# 17_-_PLUGS.net
KiCad netlist of a schematic drawn in Altium Designer
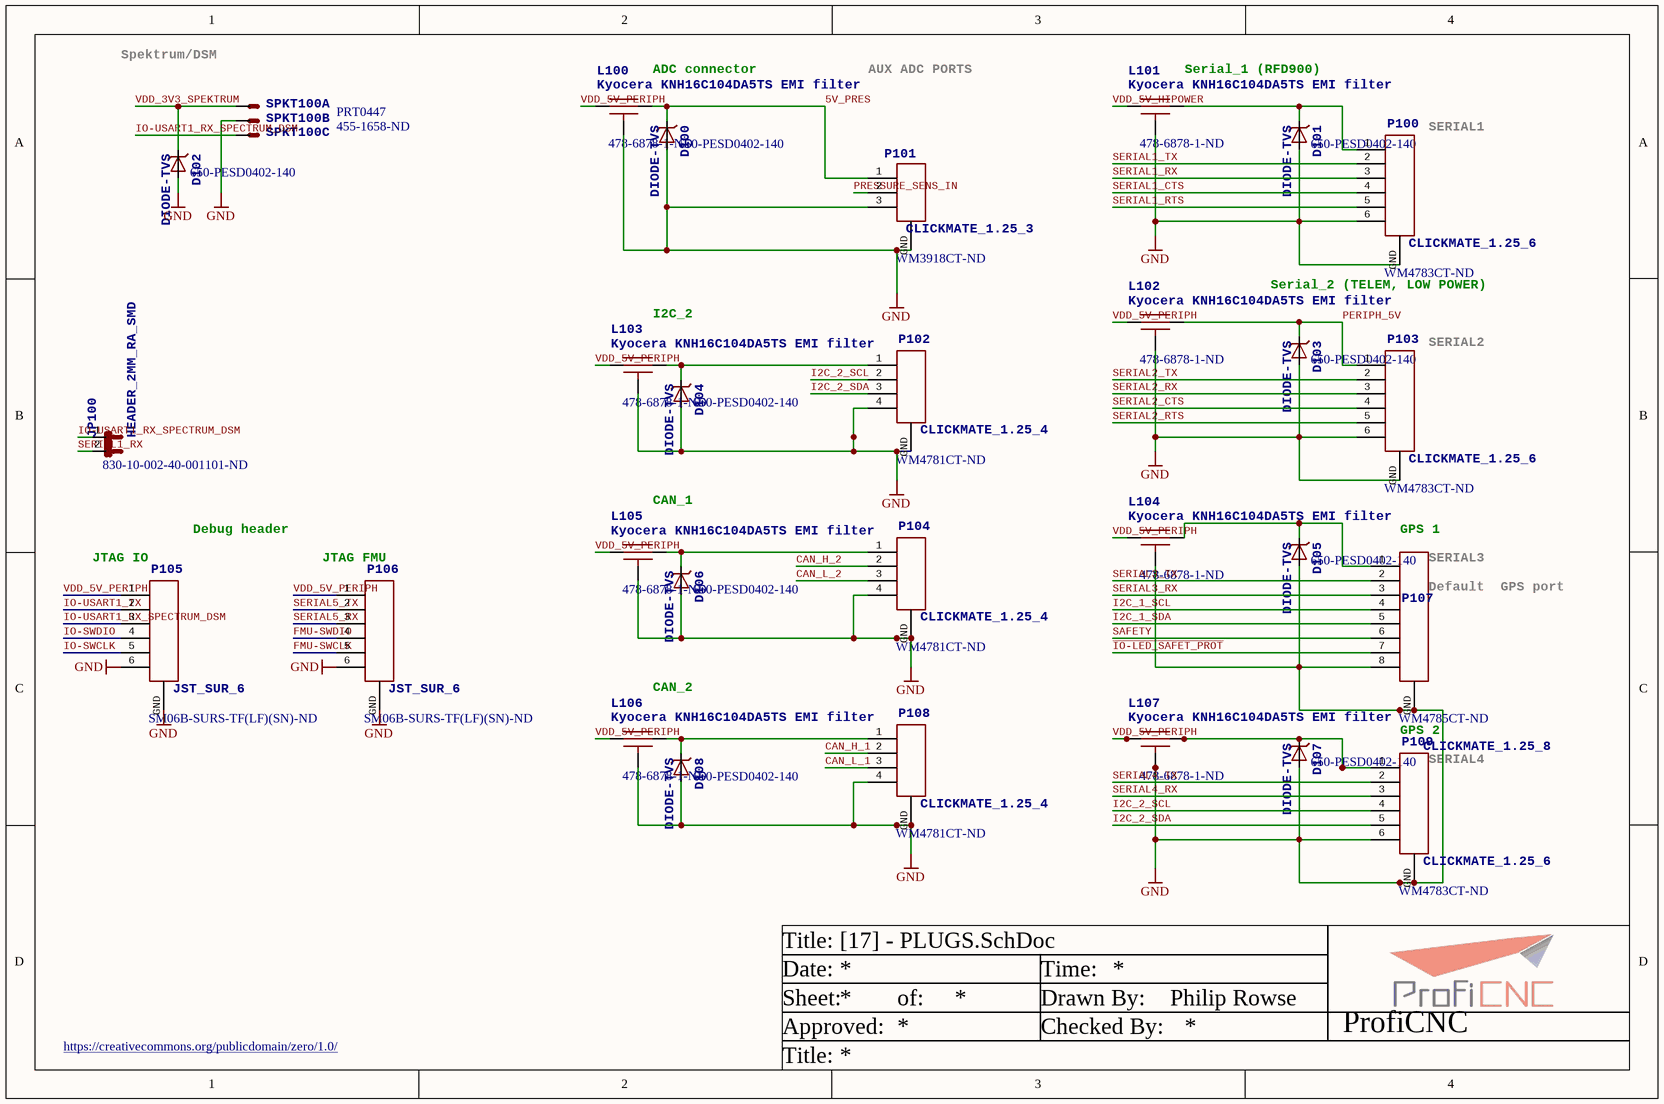
[diagram p0: [17] - PLUGS.SchDoc]

(export (version "E")
  (design (tool "Eeschema 10.0.6"))
  (components
    (comp (ref "D100")
      (value "DIODE-TVS")
      (footprint "0402-TVS")
      (description "Diode, TVS, 14VWM, 40VC, 0402, SMD")
      (fields
        (field (name "SUPPLIER PART NUMBER 1") "650-PESD0402-140")
        (field (name "3DR_PARTNO") "ECM0837")
      )
      (libsource (lib "PCA_0005_FULL_CB_REV_A") (part "DIODE-TVS"))
    )
    (comp (ref "D101")
      (value "DIODE-TVS")
      (footprint "0402-TVS")
      (description "Diode, TVS, 14VWM, 40VC, 0402, SMD")
      (fields
        (field (name "SUPPLIER PART NUMBER 1") "650-PESD0402-140")
        (field (name "3DR_PARTNO") "ECM0837")
      )
      (libsource (lib "PCA_0005_FULL_CB_REV_A") (part "DIODE-TVS"))
    )
    (comp (ref "D102")
      (value "DIODE-TVS")
      (footprint "0402-TVS")
      (description "Diode, TVS, 14VWM, 40VC, 0402, SMD")
      (fields
        (field (name "SUPPLIER PART NUMBER 1") "650-PESD0402-140")
        (field (name "3DR_PARTNO") "ECM0837")
      )
      (libsource (lib "PCA_0005_FULL_CB_REV_A") (part "DIODE-TVS"))
    )
    (comp (ref "D103")
      (value "DIODE-TVS")
      (footprint "0402-TVS")
      (description "Diode, TVS, 14VWM, 40VC, 0402, SMD")
      (fields
        (field (name "SUPPLIER PART NUMBER 1") "650-PESD0402-140")
        (field (name "3DR_PARTNO") "ECM0837")
      )
      (libsource (lib "PCA_0005_FULL_CB_REV_A") (part "DIODE-TVS"))
    )
    (comp (ref "D104")
      (value "DIODE-TVS")
      (footprint "0402-TVS")
      (description "Diode, TVS, 14VWM, 40VC, 0402, SMD")
      (fields
        (field (name "SUPPLIER PART NUMBER 1") "650-PESD0402-140")
        (field (name "3DR_PARTNO") "ECM0837")
      )
      (libsource (lib "PCA_0005_FULL_CB_REV_A") (part "DIODE-TVS"))
    )
    (comp (ref "D105")
      (value "DIODE-TVS")
      (footprint "0402-TVS")
      (description "Diode, TVS, 14VWM, 40VC, 0402, SMD")
      (fields
        (field (name "SUPPLIER PART NUMBER 1") "650-PESD0402-140")
        (field (name "3DR_PARTNO") "ECM0837")
      )
      (libsource (lib "PCA_0005_FULL_CB_REV_A") (part "DIODE-TVS"))
    )
    (comp (ref "D106")
      (value "DIODE-TVS")
      (footprint "0402-TVS")
      (description "Diode, TVS, 14VWM, 40VC, 0402, SMD")
      (fields
        (field (name "SUPPLIER PART NUMBER 1") "650-PESD0402-140")
        (field (name "3DR_PARTNO") "ECM0837")
      )
      (libsource (lib "PCA_0005_FULL_CB_REV_A") (part "DIODE-TVS"))
    )
    (comp (ref "D107")
      (value "DIODE-TVS")
      (footprint "0402-TVS")
      (description "Diode, TVS, 14VWM, 40VC, 0402, SMD")
      (fields
        (field (name "SUPPLIER PART NUMBER 1") "650-PESD0402-140")
        (field (name "3DR_PARTNO") "ECM0837")
      )
      (libsource (lib "PCA_0005_FULL_CB_REV_A") (part "DIODE-TVS"))
    )
    (comp (ref "D108")
      (value "DIODE-TVS")
      (footprint "0402-TVS")
      (description "Diode, TVS, 14VWM, 40VC, 0402, SMD")
      (fields
        (field (name "SUPPLIER PART NUMBER 1") "650-PESD0402-140")
        (field (name "3DR_PARTNO") "ECM0837")
      )
      (libsource (lib "PCA_0005_FULL_CB_REV_A") (part "DIODE-TVS"))
    )
    (comp (ref "JP100")
      (value "HEADER_2MM_RA_SMD")
      (footprint "HEADER_2MM_RA_2")
      (description "Connector, PCB, 2MM, 2Pos, R/A, SMD, Au")
      (fields
        (field (name "PARTNO") "830-10-002-40-001101")
        (field (name "SUPPLIER PART NUMBER 1") "830-10-002-40-001101-ND")
        (field (name "3DR_PARTNO") "PRT0437")
      )
      (libsource (lib "PCA_0005_FULL_CB_REV_A") (part "HEADER_2MM_RA_SMD"))
    )
    (comp (ref "L100")
      (value "Kyocera KNH16C104DA5TS EMI filter")
      (footprint "KYOCERA-KNH16-DA")
      (description "Capacitor, Filter, 0.1uF, 25V, 2A, 0603, SMD")
      (fields (field (name "SUPPLIER PART NUMBER 1") "478-6878-1-ND") (field (name "3DR_PARTNO") "ECM0719"))
      (libsource (lib "PCA_0005_FULL_CB_REV_A") (part "KNH16C104DA5TS"))
    )
    (comp (ref "L101")
      (value "Kyocera KNH16C104DA5TS EMI filter")
      (footprint "KYOCERA-KNH16-DA")
      (description "Capacitor, Filter, 0.1uF, 25V, 2A, 0603, SMD")
      (fields (field (name "SUPPLIER PART NUMBER 1") "478-6878-1-ND") (field (name "3DR_PARTNO") "ECM0719"))
      (libsource (lib "PCA_0005_FULL_CB_REV_A") (part "KNH16C104DA5TS"))
    )
    (comp (ref "L102")
      (value "Kyocera KNH16C104DA5TS EMI filter")
      (footprint "KYOCERA-KNH16-DA")
      (description "Capacitor, Filter, 0.1uF, 25V, 2A, 0603, SMD")
      (fields (field (name "SUPPLIER PART NUMBER 1") "478-6878-1-ND") (field (name "3DR_PARTNO") "ECM0719"))
      (libsource (lib "PCA_0005_FULL_CB_REV_A") (part "KNH16C104DA5TS"))
    )
    (comp (ref "L103")
      (value "Kyocera KNH16C104DA5TS EMI filter")
      (footprint "KYOCERA-KNH16-DA")
      (description "Capacitor, Filter, 0.1uF, 25V, 2A, 0603, SMD")
      (fields (field (name "SUPPLIER PART NUMBER 1") "478-6878-1-ND") (field (name "3DR_PARTNO") "ECM0719"))
      (libsource (lib "PCA_0005_FULL_CB_REV_A") (part "KNH16C104DA5TS"))
    )
    (comp (ref "L104")
      (value "Kyocera KNH16C104DA5TS EMI filter")
      (footprint "KYOCERA-KNH16-DA")
      (description "Capacitor, Filter, 0.1uF, 25V, 2A, 0603, SMD")
      (fields (field (name "SUPPLIER PART NUMBER 1") "478-6878-1-ND") (field (name "3DR_PARTNO") "ECM0719"))
      (libsource (lib "PCA_0005_FULL_CB_REV_A") (part "KNH16C104DA5TS"))
    )
    (comp (ref "L105")
      (value "Kyocera KNH16C104DA5TS EMI filter")
      (footprint "KYOCERA-KNH16-DA")
      (description "Capacitor, Filter, 0.1uF, 25V, 2A, 0603, SMD")
      (fields (field (name "SUPPLIER PART NUMBER 1") "478-6878-1-ND") (field (name "3DR_PARTNO") "ECM0719"))
      (libsource (lib "PCA_0005_FULL_CB_REV_A") (part "KNH16C104DA5TS"))
    )
    (comp (ref "L106")
      (value "Kyocera KNH16C104DA5TS EMI filter")
      (footprint "KYOCERA-KNH16-DA")
      (description "Capacitor, Filter, 0.1uF, 25V, 2A, 0603, SMD")
      (fields (field (name "SUPPLIER PART NUMBER 1") "478-6878-1-ND") (field (name "3DR_PARTNO") "ECM0719"))
      (libsource (lib "PCA_0005_FULL_CB_REV_A") (part "KNH16C104DA5TS"))
    )
    (comp (ref "L107")
      (value "Kyocera KNH16C104DA5TS EMI filter")
      (footprint "KYOCERA-KNH16-DA")
      (description "Capacitor, Filter, 0.1uF, 25V, 2A, 0603, SMD")
      (fields (field (name "SUPPLIER PART NUMBER 1") "478-6878-1-ND") (field (name "3DR_PARTNO") "ECM0719"))
      (libsource (lib "PCA_0005_FULL_CB_REV_A") (part "KNH16C104DA5TS"))
    )
    (comp (ref "P100")
      (value "CLICKMATE_1.25_6")
      (footprint "CLICKMATE_V6")
      (description "Connector, Rcpt, 6Pos, 1.25MM, W/B, VERT, SMD, Tin")
      (fields (field (name "SUPPLIER PART NUMBER 1") "WM4783CT-ND") (field (name "3DR_PARTNO") "PRT0439"))
      (libsource (lib "PCA_0005_FULL_CB_REV_A") (part "CLICKMATE_1.25_6"))
    )
    (comp (ref "P101")
      (value "CLICKMATE_1.25_3")
      (footprint "CLICKMATE_V3")
      (description "Connector, Rcpt,1.25MM,W/B,SGL,S/T,3CKT,SMD,Tin")
      (fields (field (name "SUPPLIER PART NUMBER 1") "WM3918CT-ND") (field (name "3DR_PARTNO") "PRT0440"))
      (libsource (lib "PCA_0005_FULL_CB_REV_A") (part "CLICKMATE_1.25_3"))
    )
    (comp (ref "P102")
      (value "CLICKMATE_1.25_4")
      (footprint "CLICKMATE_V4")
      (description "Connector, Rcpt, 4Pos, 1.25MM, W/B, VERT, SMD, Tin")
      (fields (field (name "SUPPLIER PART NUMBER 1") "WM4781CT-ND") (field (name "3DR_PARTNO") "PRT0441"))
      (libsource (lib "PCA_0005_FULL_CB_REV_A") (part "CLICKMATE_1.25_4"))
    )
    (comp (ref "P103")
      (value "CLICKMATE_1.25_6")
      (footprint "CLICKMATE_V6")
      (description "Connector, Rcpt, 6Pos, 1.25MM, W/B, VERT, SMD, Tin")
      (fields (field (name "SUPPLIER PART NUMBER 1") "WM4783CT-ND") (field (name "3DR_PARTNO") "PRT0439"))
      (libsource (lib "PCA_0005_FULL_CB_REV_A") (part "CLICKMATE_1.25_6"))
    )
    (comp (ref "P104")
      (value "CLICKMATE_1.25_4")
      (footprint "CLICKMATE_V4")
      (description "Connector, Rcpt, 4Pos, 1.25MM, W/B, VERT, SMD, Tin")
      (fields (field (name "SUPPLIER PART NUMBER 1") "WM4781CT-ND") (field (name "3DR_PARTNO") "PRT0441"))
      (libsource (lib "PCA_0005_FULL_CB_REV_A") (part "CLICKMATE_1.25_4"))
    )
    (comp (ref "P105")
      (value "JST_SUR_6")
      (footprint "JST_SUR_H6")
      (description "Connector, Header, 6Pos, .8mm IDC, R/A, SMD, Tin")
      (fields
        (field (name "SUPPLIER PART NUMBER 1") "SM06B-SURS-TF(LF)(SN)-ND")
        (field (name "3DR_PARTNO") "PRT0442")
      )
      (libsource (lib "PCA_0005_FULL_CB_REV_A") (part "JST_SUR_6"))
    )
    (comp (ref "P106")
      (value "JST_SUR_6")
      (footprint "JST_SUR_H6")
      (description "Connector, Header, 6Pos, .8mm IDC, R/A, SMD, Tin")
      (fields
        (field (name "SUPPLIER PART NUMBER 1") "SM06B-SURS-TF(LF)(SN)-ND")
        (field (name "3DR_PARTNO") "PRT0442")
      )
      (libsource (lib "PCA_0005_FULL_CB_REV_A") (part "JST_SUR_6"))
    )
    (comp (ref "P107")
      (value "CLICKMATE_1.25_8")
      (footprint "CLICKMATE_V8")
      (description "Connector, Rcpt, 8Pos, 1.25MM, W/B, VERT, SMD, Tin")
      (fields (field (name "SUPPLIER PART NUMBER 1") "WM4785CT-ND") (field (name "3DR_PARTNO") "PRT0443"))
      (libsource (lib "PCA_0005_FULL_CB_REV_A") (part "CLICKMATE_1.25_8"))
    )
    (comp (ref "P108")
      (value "CLICKMATE_1.25_4")
      (footprint "CLICKMATE_V4")
      (description "Connector, Rcpt, 4Pos, 1.25MM, W/B, VERT, SMD, Tin")
      (fields (field (name "SUPPLIER PART NUMBER 1") "WM4781CT-ND") (field (name "3DR_PARTNO") "PRT0441"))
      (libsource (lib "PCA_0005_FULL_CB_REV_A") (part "CLICKMATE_1.25_4"))
    )
    (comp (ref "P109")
      (value "CLICKMATE_1.25_6")
      (footprint "CLICKMATE_V6")
      (description "Connector, Rcpt, 6Pos, 1.25MM, W/B, VERT, SMD, Tin")
      (fields (field (name "SUPPLIER PART NUMBER 1") "WM4783CT-ND") (field (name "3DR_PARTNO") "PRT0439"))
      (libsource (lib "PCA_0005_FULL_CB_REV_A") (part "CLICKMATE_1.25_6"))
    )
    (comp (ref "SPKT100")
      (value "CONN_SPEKTRUM_RX-TH")
      (footprint "B3B-ZR")
      (description "Spektrum RX connector; JST ZH series S3B-ZR-SM4A-TF")
      (fields
        (field (name "PARTNO") "B3B-ZR(LF)(SN)")
        (field (name "3DR_PARTNO") "PRT0447")
        (field (name "SUPPLIER PART NUMBER 1") "455-1658-ND")
      )
      (libsource (lib "PCA_0005_FULL_CB_REV_A") (part "CONN_SPEKTRUM_RX-TH"))
    )
  )
  (nets
    (net (code "1") (name "/5V_PRES") (class "Default")
      (node (ref "D100") (pin "C") (pinfunction "C_C") (pintype "passive"))
      (node (ref "L100") (pin "P$2") (pinfunction "P$2_P$2") (pintype "passive"))
      (node (ref "P101") (pin "1") (pinfunction "1_1") (pintype "passive"))
    )
    (net (code "2") (name "/CAN_H_1") (class "Default")
      (node (ref "P108") (pin "2") (pinfunction "2_2") (pintype "passive"))
    )
    (net (code "3") (name "/CAN_H_2") (class "Default")
      (node (ref "P104") (pin "2") (pinfunction "2_2") (pintype "passive"))
    )
    (net (code "4") (name "/CAN_L_1") (class "Default")
      (node (ref "P108") (pin "3") (pinfunction "3_3") (pintype "passive"))
    )
    (net (code "5") (name "/CAN_L_2") (class "Default")
      (node (ref "P104") (pin "3") (pinfunction "3_3") (pintype "passive"))
    )
    (net (code "6") (name "/FMU-SWCLK") (class "Default")
      (node (ref "P106") (pin "5") (pinfunction "5_5") (pintype "passive"))
    )
    (net (code "7") (name "/FMU-SWDIO") (class "Default")
      (node (ref "P106") (pin "4") (pinfunction "4_4") (pintype "passive"))
    )
    (net (code "8") (name "/I2C_1_SCL") (class "Default")
      (node (ref "P107") (pin "4") (pinfunction "4_4") (pintype "passive"))
    )
    (net (code "9") (name "/I2C_1_SDA") (class "Default")
      (node (ref "P107") (pin "5") (pinfunction "5_5") (pintype "passive"))
    )
    (net (code "10") (name "/I2C_2_SCL") (class "Default")
      (node (ref "P102") (pin "2") (pinfunction "2_2") (pintype "passive"))
      (node (ref "P109") (pin "4") (pinfunction "4_4") (pintype "passive"))
    )
    (net (code "11") (name "/I2C_2_SDA") (class "Default")
      (node (ref "P102") (pin "3") (pinfunction "3_3") (pintype "passive"))
      (node (ref "P109") (pin "5") (pinfunction "5_5") (pintype "passive"))
    )
    (net (code "12") (name "/IO-SWCLK") (class "Default")
      (node (ref "P105") (pin "5") (pinfunction "5_5") (pintype "passive"))
    )
    (net (code "13") (name "/IO-SWDIO") (class "Default")
      (node (ref "P105") (pin "4") (pinfunction "4_4") (pintype "passive"))
    )
    (net (code "14") (name "/IO-USART1_RX_SPECTRUM_DSM") (class "Default")
      (node (ref "JP100") (pin "1") (pinfunction "1_1") (pintype "passive"))
      (node (ref "P105") (pin "3") (pinfunction "3_3") (pintype "passive"))
      (node (ref "SPKT100") (pin "1") (pinfunction "S_1") (pintype "passive"))
    )
    (net (code "15") (name "/IO-USART1_TX") (class "Default")
      (node (ref "P105") (pin "2") (pinfunction "2_2") (pintype "passive"))
    )
    (net (code "16") (name "/PERIPH_5V") (class "Default")
      (node (ref "D103") (pin "C") (pinfunction "C_C") (pintype "passive"))
      (node (ref "L102") (pin "P$2") (pinfunction "P$2_P$2") (pintype "passive"))
      (node (ref "P103") (pin "1") (pinfunction "1_1") (pintype "passive"))
    )
    (net (code "17") (name "/PRESSURE_SENS_IN") (class "Default")
      (node (ref "P101") (pin "2") (pinfunction "2_2") (pintype "passive"))
    )
    (net (code "18") (name "/SAFETY") (class "Default")
      (node (ref "P107") (pin "6") (pinfunction "6_6") (pintype "passive"))
    )
    (net (code "19") (name "/SERIAL1_CTS") (class "Default")
      (node (ref "P100") (pin "4") (pinfunction "4_4") (pintype "passive"))
    )
    (net (code "20") (name "/SERIAL1_RTS") (class "Default")
      (node (ref "P100") (pin "5") (pinfunction "5_5") (pintype "passive"))
    )
    (net (code "21") (name "/SERIAL1_RX") (class "Default")
      (node (ref "JP100") (pin "2") (pinfunction "2_2") (pintype "passive"))
      (node (ref "P100") (pin "3") (pinfunction "3_3") (pintype "passive"))
    )
    (net (code "22") (name "/SERIAL1_TX") (class "Default")
      (node (ref "P100") (pin "2") (pinfunction "2_2") (pintype "passive"))
    )
    (net (code "23") (name "/SERIAL2_CTS") (class "Default")
      (node (ref "P103") (pin "4") (pinfunction "4_4") (pintype "passive"))
    )
    (net (code "24") (name "/SERIAL2_RTS") (class "Default")
      (node (ref "P103") (pin "5") (pinfunction "5_5") (pintype "passive"))
    )
    (net (code "25") (name "/SERIAL2_RX") (class "Default")
      (node (ref "P103") (pin "3") (pinfunction "3_3") (pintype "passive"))
    )
    (net (code "26") (name "/SERIAL2_TX") (class "Default")
      (node (ref "P103") (pin "2") (pinfunction "2_2") (pintype "passive"))
    )
    (net (code "27") (name "/SERIAL3_RX") (class "Default")
      (node (ref "P107") (pin "3") (pinfunction "3_3") (pintype "passive"))
    )
    (net (code "28") (name "/SERIAL3_TX") (class "Default")
      (node (ref "P107") (pin "2") (pinfunction "2_2") (pintype "passive"))
    )
    (net (code "29") (name "/SERIAL4_RX") (class "Default")
      (node (ref "P109") (pin "3") (pinfunction "3_3") (pintype "passive"))
    )
    (net (code "30") (name "/SERIAL4_TX") (class "Default")
      (node (ref "P109") (pin "2") (pinfunction "2_2") (pintype "passive"))
    )
    (net (code "31") (name "/SERIAL5_RX") (class "Default")
      (node (ref "P106") (pin "3") (pinfunction "3_3") (pintype "passive"))
    )
    (net (code "32") (name "/SERIAL5_TX") (class "Default")
      (node (ref "P106") (pin "2") (pinfunction "2_2") (pintype "passive"))
    )
    (net (code "33") (name "/VDD_3V3_SPEKTRUM") (class "Default")
      (node (ref "D102") (pin "C") (pinfunction "C_C") (pintype "passive"))
      (node (ref "SPKT100") (pin "3") (pinfunction "S_3") (pintype "passive"))
    )
    (net (code "34") (name "/VDD_5V_HIPOWER") (class "Default")
      (node (ref "L101") (pin "P$1") (pinfunction "P$1_P$1") (pintype "passive"))
    )
    (net (code "35") (name "/VDD_5V_PERIPH") (class "Default")
      (node (ref "L100") (pin "P$1") (pinfunction "P$1_P$1") (pintype "passive"))
      (node (ref "L102") (pin "P$1") (pinfunction "P$1_P$1") (pintype "passive"))
      (node (ref "L103") (pin "P$1") (pinfunction "P$1_P$1") (pintype "passive"))
      (node (ref "L104") (pin "P$1") (pinfunction "P$1_P$1") (pintype "passive"))
      (node (ref "L105") (pin "P$1") (pinfunction "P$1_P$1") (pintype "passive"))
      (node (ref "L106") (pin "P$1") (pinfunction "P$1_P$1") (pintype "passive"))
      (node (ref "L107") (pin "P$1") (pinfunction "P$1_P$1") (pintype "passive"))
      (node (ref "P105") (pin "1") (pinfunction "1_1") (pintype "passive"))
      (node (ref "P106") (pin "1") (pinfunction "1_1") (pintype "passive"))
    )
    (net (code "36") (name "/~{IO-LED_SAFET_PROT}") (class "Default")
      (node (ref "P107") (pin "7") (pinfunction "7_7") (pintype "passive"))
    )
    (net (code "37") (name "GND") (class "Default")
      (node (ref "D100") (pin "A") (pinfunction "A_A") (pintype "passive"))
      (node (ref "D101") (pin "A") (pinfunction "A_A") (pintype "passive"))
      (node (ref "D102") (pin "A") (pinfunction "A_A") (pintype "passive"))
      (node (ref "D103") (pin "A") (pinfunction "A_A") (pintype "passive"))
      (node (ref "D104") (pin "A") (pinfunction "A_A") (pintype "passive"))
      (node (ref "D105") (pin "A") (pinfunction "A_A") (pintype "passive"))
      (node (ref "D106") (pin "A") (pinfunction "A_A") (pintype "passive"))
      (node (ref "D107") (pin "A") (pinfunction "A_A") (pintype "passive"))
      (node (ref "D108") (pin "A") (pinfunction "A_A") (pintype "passive"))
      (node (ref "L100") (pin "GND") (pinfunction "GND_GND") (pintype "passive"))
      (node (ref "L101") (pin "GND") (pinfunction "GND_GND") (pintype "passive"))
      (node (ref "L102") (pin "GND") (pinfunction "GND_GND") (pintype "passive"))
      (node (ref "L103") (pin "GND") (pinfunction "GND_GND") (pintype "passive"))
      (node (ref "L104") (pin "GND") (pinfunction "GND_GND") (pintype "passive"))
      (node (ref "L105") (pin "GND") (pinfunction "GND_GND") (pintype "passive"))
      (node (ref "L106") (pin "GND") (pinfunction "GND_GND") (pintype "passive"))
      (node (ref "L107") (pin "GND") (pinfunction "GND_GND") (pintype "passive"))
      (node (ref "P100") (pin "6") (pinfunction "6_6") (pintype "passive"))
      (node (ref "P100") (pin "GND") (pinfunction "GND_GND") (pintype "passive"))
      (node (ref "P101") (pin "3") (pinfunction "3_3") (pintype "passive"))
      (node (ref "P101") (pin "GND") (pinfunction "GND_GND") (pintype "passive"))
      (node (ref "P102") (pin "4") (pinfunction "4_4") (pintype "passive"))
      (node (ref "P102") (pin "GND") (pinfunction "GND_GND") (pintype "passive"))
      (node (ref "P103") (pin "6") (pinfunction "6_6") (pintype "passive"))
      (node (ref "P103") (pin "GND") (pinfunction "GND_GND") (pintype "passive"))
      (node (ref "P104") (pin "4") (pinfunction "4_4") (pintype "passive"))
      (node (ref "P104") (pin "GND") (pinfunction "GND_GND") (pintype "passive"))
      (node (ref "P105") (pin "6") (pinfunction "6_6") (pintype "passive"))
      (node (ref "P105") (pin "GND") (pinfunction "GND_GND") (pintype "passive"))
      (node (ref "P106") (pin "6") (pinfunction "6_6") (pintype "passive"))
      (node (ref "P106") (pin "GND") (pinfunction "GND_GND") (pintype "passive"))
      (node (ref "P107") (pin "8") (pinfunction "8_8") (pintype "passive"))
      (node (ref "P107") (pin "GND") (pinfunction "GND_GND") (pintype "passive"))
      (node (ref "P108") (pin "4") (pinfunction "4_4") (pintype "passive"))
      (node (ref "P108") (pin "GND") (pinfunction "GND_GND") (pintype "passive"))
      (node (ref "P109") (pin "6") (pinfunction "6_6") (pintype "passive"))
      (node (ref "P109") (pin "GND") (pinfunction "GND_GND") (pintype "passive"))
      (node (ref "SPKT100") (pin "2") (pinfunction "S_2") (pintype "passive"))
    )
    (net (code "38") (name "Net-(D101-PadC)") (class "Default")
      (node (ref "D101") (pin "C") (pinfunction "C_C") (pintype "passive"))
      (node (ref "L101") (pin "P$2") (pinfunction "P$2_P$2") (pintype "passive"))
      (node (ref "P100") (pin "1") (pinfunction "1_1") (pintype "passive"))
    )
    (net (code "39") (name "Net-(D104-PadC)") (class "Default")
      (node (ref "D104") (pin "C") (pinfunction "C_C") (pintype "passive"))
      (node (ref "L103") (pin "P$2") (pinfunction "P$2_P$2") (pintype "passive"))
      (node (ref "P102") (pin "1") (pinfunction "1_1") (pintype "passive"))
    )
    (net (code "40") (name "Net-(D105-PadC)") (class "Default")
      (node (ref "D105") (pin "C") (pinfunction "C_C") (pintype "passive"))
      (node (ref "L104") (pin "P$2") (pinfunction "P$2_P$2") (pintype "passive"))
      (node (ref "P107") (pin "1") (pinfunction "1_1") (pintype "passive"))
    )
    (net (code "41") (name "Net-(D106-PadC)") (class "Default")
      (node (ref "D106") (pin "C") (pinfunction "C_C") (pintype "passive"))
      (node (ref "L105") (pin "P$2") (pinfunction "P$2_P$2") (pintype "passive"))
      (node (ref "P104") (pin "1") (pinfunction "1_1") (pintype "passive"))
    )
    (net (code "42") (name "Net-(D107-PadC)") (class "Default")
      (node (ref "D107") (pin "C") (pinfunction "C_C") (pintype "passive"))
      (node (ref "L107") (pin "P$2") (pinfunction "P$2_P$2") (pintype "passive"))
      (node (ref "P109") (pin "1") (pinfunction "1_1") (pintype "passive"))
    )
    (net (code "43") (name "Net-(D108-PadC)") (class "Default")
      (node (ref "D108") (pin "C") (pinfunction "C_C") (pintype "passive"))
      (node (ref "L106") (pin "P$2") (pinfunction "P$2_P$2") (pintype "passive"))
      (node (ref "P108") (pin "1") (pinfunction "1_1") (pintype "passive"))
    )
  )
)
